# buttons.net
KiCad netlist of a schematic drawn in Altium Designer
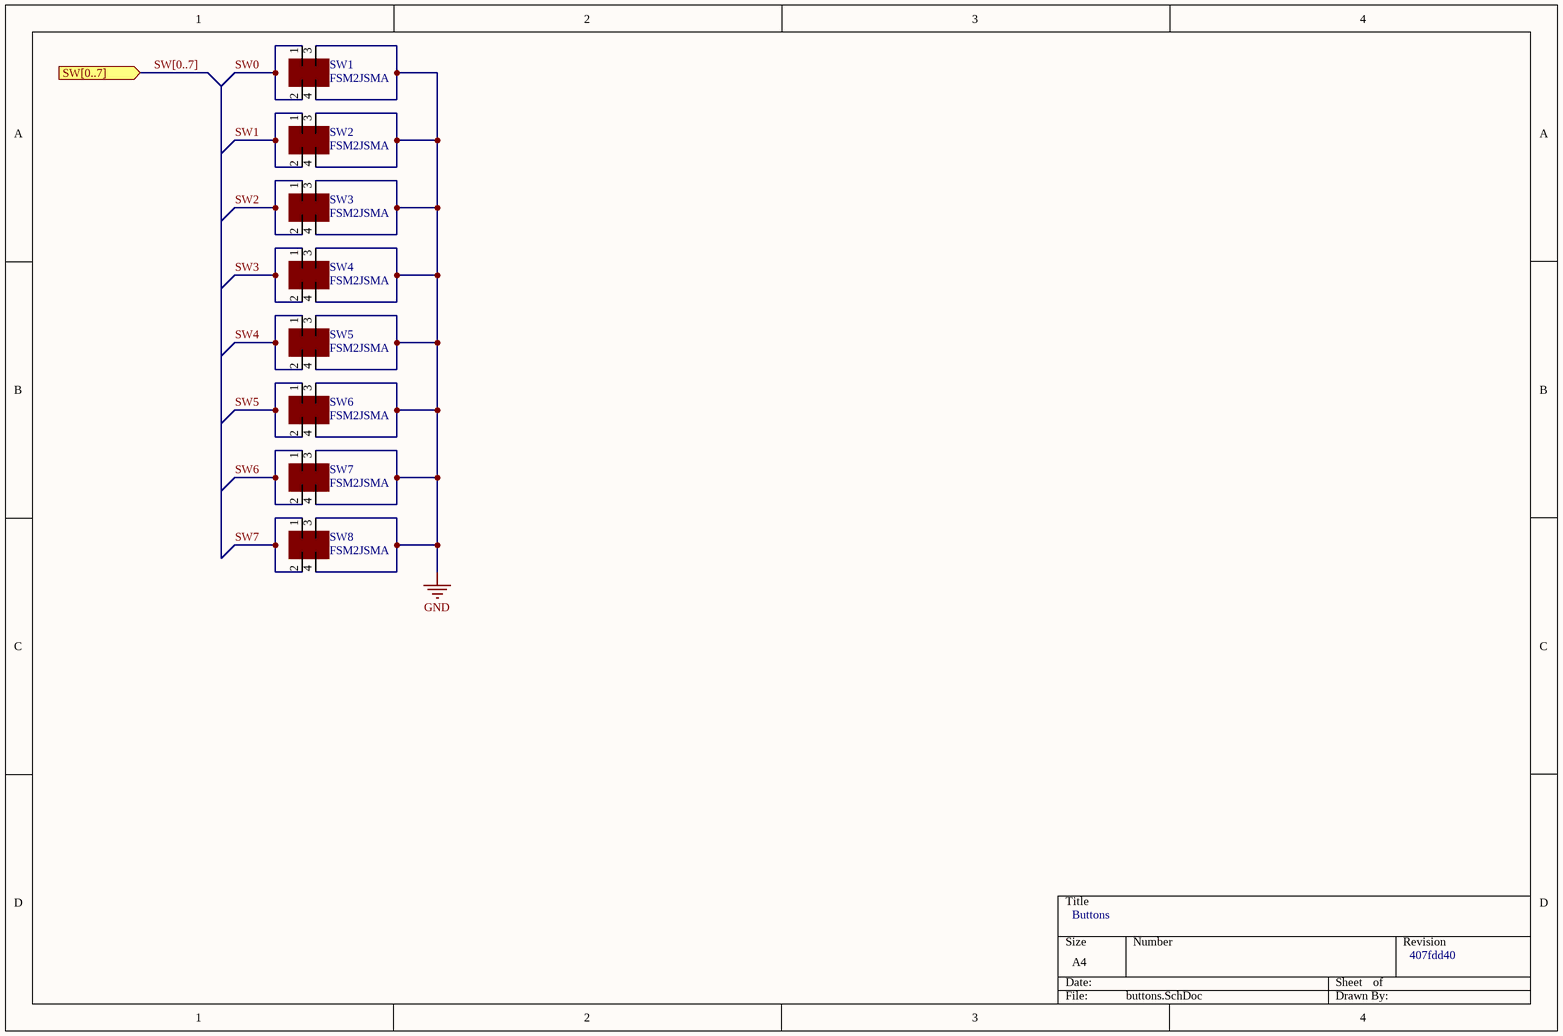
[diagram p0: buttons.SchDoc]

(export (version "E")
  (design (tool "Eeschema 10.0.6"))
  (components
    (comp (ref "SW1")
      (value "FSM2JSMA")
      (footprint "Button")
      (libsource (lib "switches") (part "switch-button"))
    )
    (comp (ref "SW2")
      (value "FSM2JSMA")
      (footprint "Button")
      (libsource (lib "switches") (part "switch-button"))
    )
    (comp (ref "SW3")
      (value "FSM2JSMA")
      (footprint "Button")
      (libsource (lib "switches") (part "switch-button"))
    )
    (comp (ref "SW4")
      (value "FSM2JSMA")
      (footprint "Button")
      (libsource (lib "switches") (part "switch-button"))
    )
    (comp (ref "SW5")
      (value "FSM2JSMA")
      (footprint "Button")
      (libsource (lib "switches") (part "switch-button"))
    )
    (comp (ref "SW6")
      (value "FSM2JSMA")
      (footprint "Button")
      (libsource (lib "switches") (part "switch-button"))
    )
    (comp (ref "SW7")
      (value "FSM2JSMA")
      (footprint "Button")
      (libsource (lib "switches") (part "switch-button"))
    )
    (comp (ref "SW8")
      (value "FSM2JSMA")
      (footprint "Button")
      (libsource (lib "switches") (part "switch-button"))
    )
  )
  (nets
    (net (code "1") (name "/SW0") (class "Default")
      (node (ref "SW1") (pin "1") (pinfunction "1_1") (pintype "passive"))
      (node (ref "SW1") (pin "2") (pinfunction "2_2") (pintype "passive"))
    )
    (net (code "2") (name "/SW1") (class "Default")
      (node (ref "SW2") (pin "1") (pinfunction "1_1") (pintype "passive"))
      (node (ref "SW2") (pin "2") (pinfunction "2_2") (pintype "passive"))
    )
    (net (code "3") (name "/SW2") (class "Default")
      (node (ref "SW3") (pin "1") (pinfunction "1_1") (pintype "passive"))
      (node (ref "SW3") (pin "2") (pinfunction "2_2") (pintype "passive"))
    )
    (net (code "4") (name "/SW3") (class "Default")
      (node (ref "SW4") (pin "1") (pinfunction "1_1") (pintype "passive"))
      (node (ref "SW4") (pin "2") (pinfunction "2_2") (pintype "passive"))
    )
    (net (code "5") (name "/SW4") (class "Default")
      (node (ref "SW5") (pin "1") (pinfunction "1_1") (pintype "passive"))
      (node (ref "SW5") (pin "2") (pinfunction "2_2") (pintype "passive"))
    )
    (net (code "6") (name "/SW5") (class "Default")
      (node (ref "SW6") (pin "1") (pinfunction "1_1") (pintype "passive"))
      (node (ref "SW6") (pin "2") (pinfunction "2_2") (pintype "passive"))
    )
    (net (code "7") (name "/SW6") (class "Default")
      (node (ref "SW7") (pin "1") (pinfunction "1_1") (pintype "passive"))
      (node (ref "SW7") (pin "2") (pinfunction "2_2") (pintype "passive"))
    )
    (net (code "8") (name "/SW7") (class "Default")
      (node (ref "SW8") (pin "1") (pinfunction "1_1") (pintype "passive"))
      (node (ref "SW8") (pin "2") (pinfunction "2_2") (pintype "passive"))
    )
    (net (code "10") (name "GND") (class "Default")
      (node (ref "SW1") (pin "3") (pinfunction "3_3") (pintype "passive"))
      (node (ref "SW1") (pin "4") (pinfunction "4_4") (pintype "passive"))
      (node (ref "SW2") (pin "3") (pinfunction "3_3") (pintype "passive"))
      (node (ref "SW2") (pin "4") (pinfunction "4_4") (pintype "passive"))
      (node (ref "SW3") (pin "3") (pinfunction "3_3") (pintype "passive"))
      (node (ref "SW3") (pin "4") (pinfunction "4_4") (pintype "passive"))
      (node (ref "SW4") (pin "3") (pinfunction "3_3") (pintype "passive"))
      (node (ref "SW4") (pin "4") (pinfunction "4_4") (pintype "passive"))
      (node (ref "SW5") (pin "3") (pinfunction "3_3") (pintype "passive"))
      (node (ref "SW5") (pin "4") (pinfunction "4_4") (pintype "passive"))
      (node (ref "SW6") (pin "3") (pinfunction "3_3") (pintype "passive"))
      (node (ref "SW6") (pin "4") (pinfunction "4_4") (pintype "passive"))
      (node (ref "SW7") (pin "3") (pinfunction "3_3") (pintype "passive"))
      (node (ref "SW7") (pin "4") (pinfunction "4_4") (pintype "passive"))
      (node (ref "SW8") (pin "3") (pinfunction "3_3") (pintype "passive"))
      (node (ref "SW8") (pin "4") (pinfunction "4_4") (pintype "passive"))
    )
  )
)
